# simple_encoder.net
KiCad netlist of a schematic drawn in EAGLE
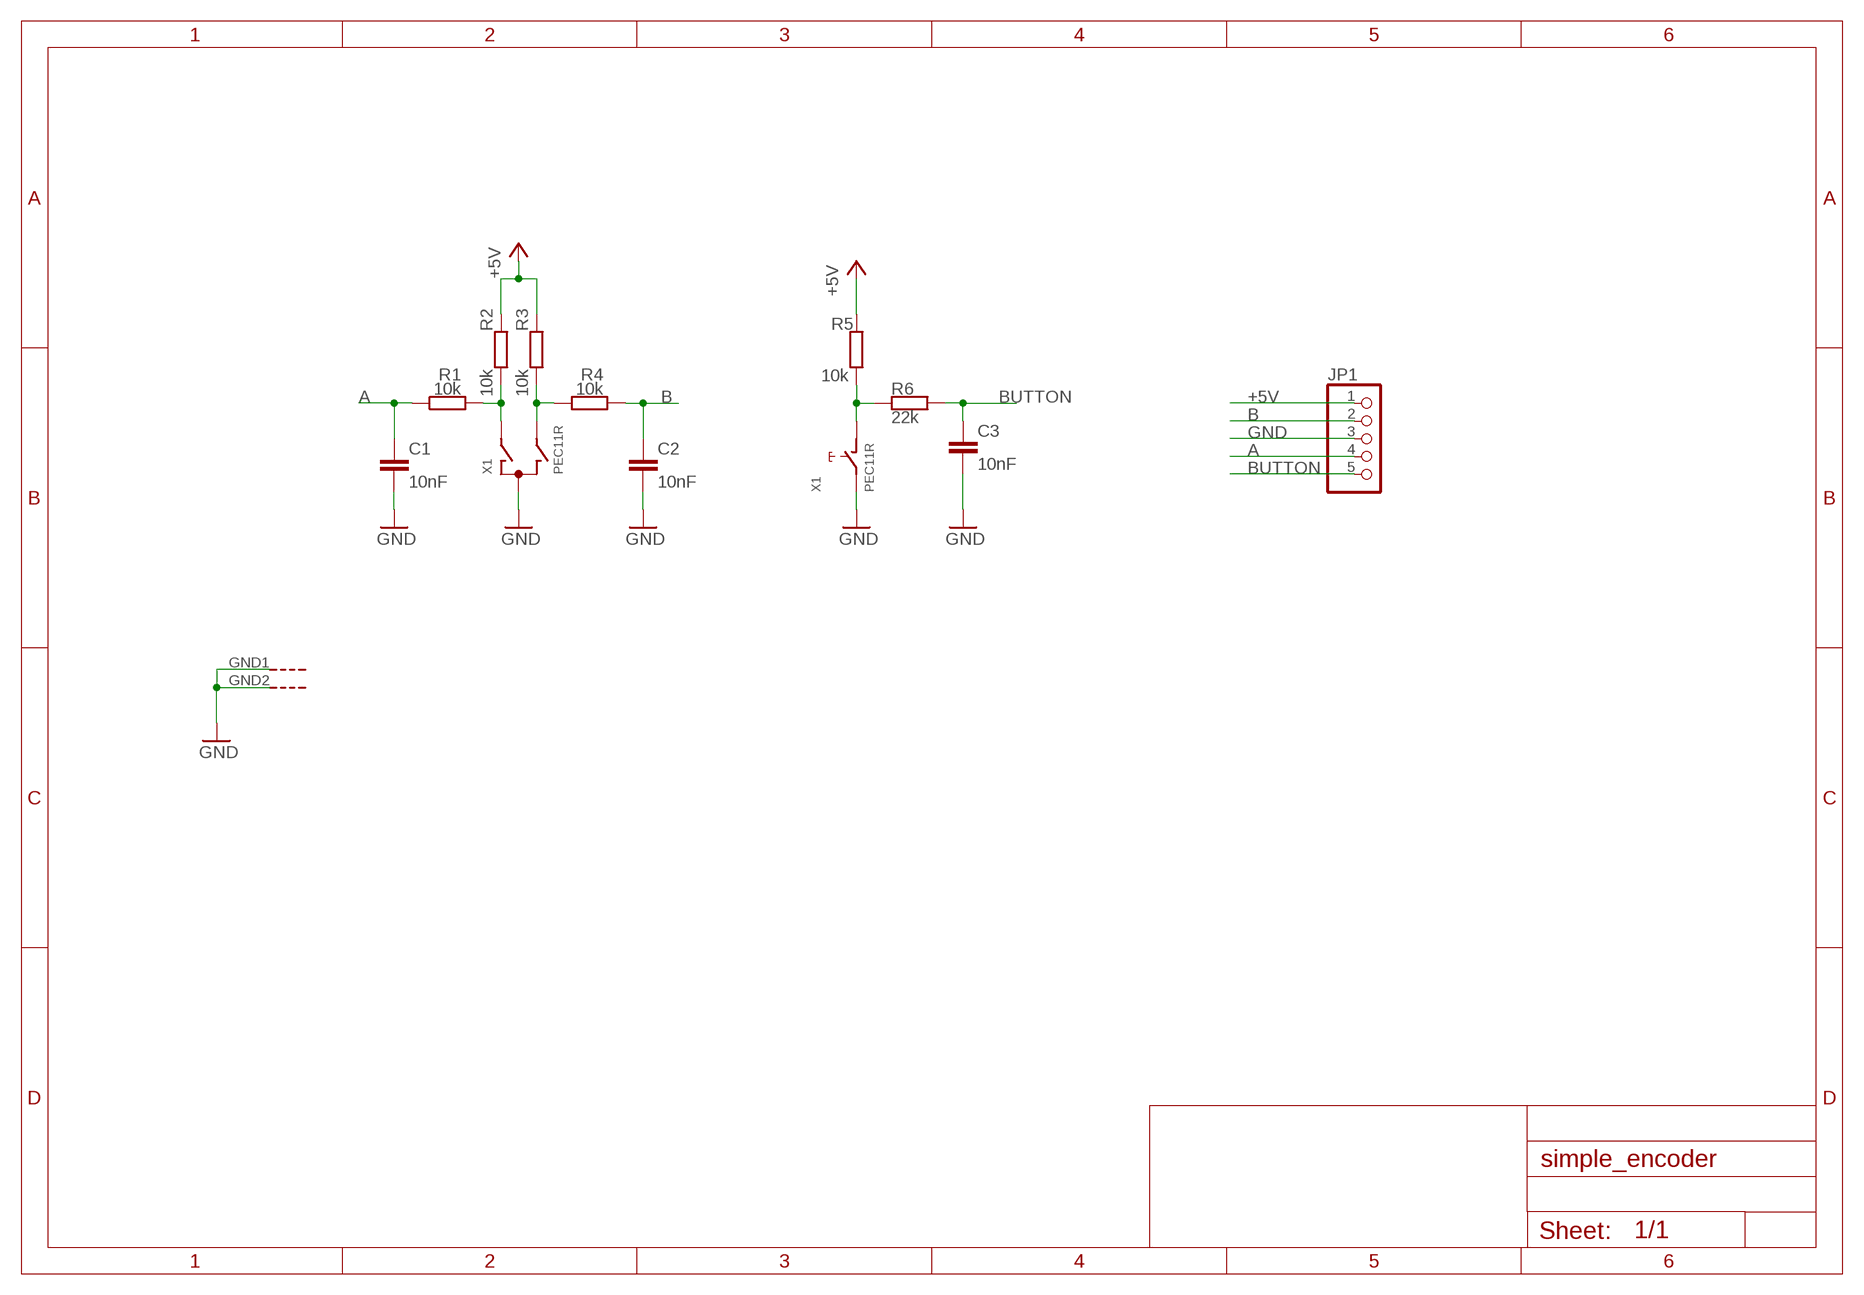
[diagram p0: schematic, sheet 1]

(export (version "E")
  (design (tool "Eeschema 10.0.6"))
  (components
    (comp (ref "C1")
      (value "10nF")
      (footprint "eagle-import:C0805")
      (libsource (lib "eagle-import") (part "C-EUC0805"))
    )
    (comp (ref "C2")
      (value "10nF")
      (footprint "eagle-import:C0805")
      (libsource (lib "eagle-import") (part "C-EUC0805"))
    )
    (comp (ref "C3")
      (value "10nF")
      (footprint "eagle-import:C0805")
      (libsource (lib "eagle-import") (part "C-EUC0805"))
    )
    (comp (ref "JP1")
      (value "PINHD-1X5")
      (footprint "eagle-import:1X05")
      (libsource (lib "eagle-import") (part "PINHD-1X5"))
    )
    (comp (ref "R1")
      (value "10k")
      (footprint "eagle-import:R0805")
      (libsource (lib "eagle-import") (part "R-EU_R0805"))
    )
    (comp (ref "R2")
      (value "10k")
      (footprint "eagle-import:R0805")
      (libsource (lib "eagle-import") (part "R-EU_R0805"))
    )
    (comp (ref "R3")
      (value "10k")
      (footprint "eagle-import:R0805")
      (libsource (lib "eagle-import") (part "R-EU_R0805"))
    )
    (comp (ref "R4")
      (value "10k")
      (footprint "eagle-import:R0805")
      (libsource (lib "eagle-import") (part "R-EU_R0805"))
    )
    (comp (ref "R5")
      (value "10k")
      (footprint "eagle-import:R0805")
      (libsource (lib "eagle-import") (part "R-EU_R0805"))
    )
    (comp (ref "R6")
      (value "22k")
      (footprint "eagle-import:R0805")
      (libsource (lib "eagle-import") (part "R-EU_R0805"))
    )
    (comp (ref "X1")
      (value "PEC11R")
      (footprint "eagle-import:PEC11R")
      (libsource (lib "eagle-import") (part "PEC11R"))
    )
  )
  (nets
    (net (code "1") (name "+5V") (class "Default")
      (node (ref "JP1") (pin "1") (pinfunction "1_1") (pintype "passive"))
      (node (ref "R2") (pin "2") (pinfunction "2_2") (pintype "passive"))
      (node (ref "R3") (pin "2") (pinfunction "2_2") (pintype "passive"))
      (node (ref "R5") (pin "2") (pinfunction "2_2") (pintype "passive"))
    )
    (net (code "2") (name "/A") (class "Default")
      (node (ref "C1") (pin "1") (pinfunction "1_1") (pintype "passive"))
      (node (ref "JP1") (pin "4") (pinfunction "4_4") (pintype "passive"))
      (node (ref "R1") (pin "1") (pinfunction "1_1") (pintype "passive"))
    )
    (net (code "3") (name "/B") (class "Default")
      (node (ref "C2") (pin "1") (pinfunction "1_1") (pintype "passive"))
      (node (ref "JP1") (pin "2") (pinfunction "2_2") (pintype "passive"))
      (node (ref "R4") (pin "2") (pinfunction "2_2") (pintype "passive"))
    )
    (net (code "4") (name "/BUTTON") (class "Default")
      (node (ref "C3") (pin "1") (pinfunction "1_1") (pintype "passive"))
      (node (ref "JP1") (pin "5") (pinfunction "5_5") (pintype "passive"))
      (node (ref "R6") (pin "2") (pinfunction "2_2") (pintype "passive"))
    )
    (net (code "5") (name "GND") (class "Default")
      (node (ref "C1") (pin "2") (pinfunction "2_2") (pintype "passive"))
      (node (ref "C2") (pin "2") (pinfunction "2_2") (pintype "passive"))
      (node (ref "C3") (pin "2") (pinfunction "2_2") (pintype "passive"))
      (node (ref "JP1") (pin "3") (pinfunction "3_3") (pintype "passive"))
      (node (ref "X1") (pin "C") (pinfunction "C_C") (pintype "passive"))
      (node (ref "X1") (pin "E") (pinfunction "E_E") (pintype "passive"))
      (node (ref "X1") (pin "GND1") (pinfunction "G_GND1") (pintype "passive"))
      (node (ref "X1") (pin "GND2") (pinfunction "G_GND2") (pintype "passive"))
    )
    (net (code "6") (name "Net-(R1-Pad2)") (class "Default")
      (node (ref "R1") (pin "2") (pinfunction "2_2") (pintype "passive"))
      (node (ref "R2") (pin "1") (pinfunction "1_1") (pintype "passive"))
      (node (ref "X1") (pin "A") (pinfunction "A_A") (pintype "passive"))
    )
    (net (code "7") (name "Net-(R3-Pad1)") (class "Default")
      (node (ref "R3") (pin "1") (pinfunction "1_1") (pintype "passive"))
      (node (ref "R4") (pin "1") (pinfunction "1_1") (pintype "passive"))
      (node (ref "X1") (pin "B") (pinfunction "B_B") (pintype "passive"))
    )
    (net (code "8") (name "Net-(R5-Pad1)") (class "Default")
      (node (ref "R5") (pin "1") (pinfunction "1_1") (pintype "passive"))
      (node (ref "R6") (pin "1") (pinfunction "1_1") (pintype "passive"))
      (node (ref "X1") (pin "D") (pinfunction "D_D") (pintype "passive"))
    )
  )
)
